# XM-JLINK-V1_0_0.net
KiCad netlist of a schematic drawn in Altium Designer
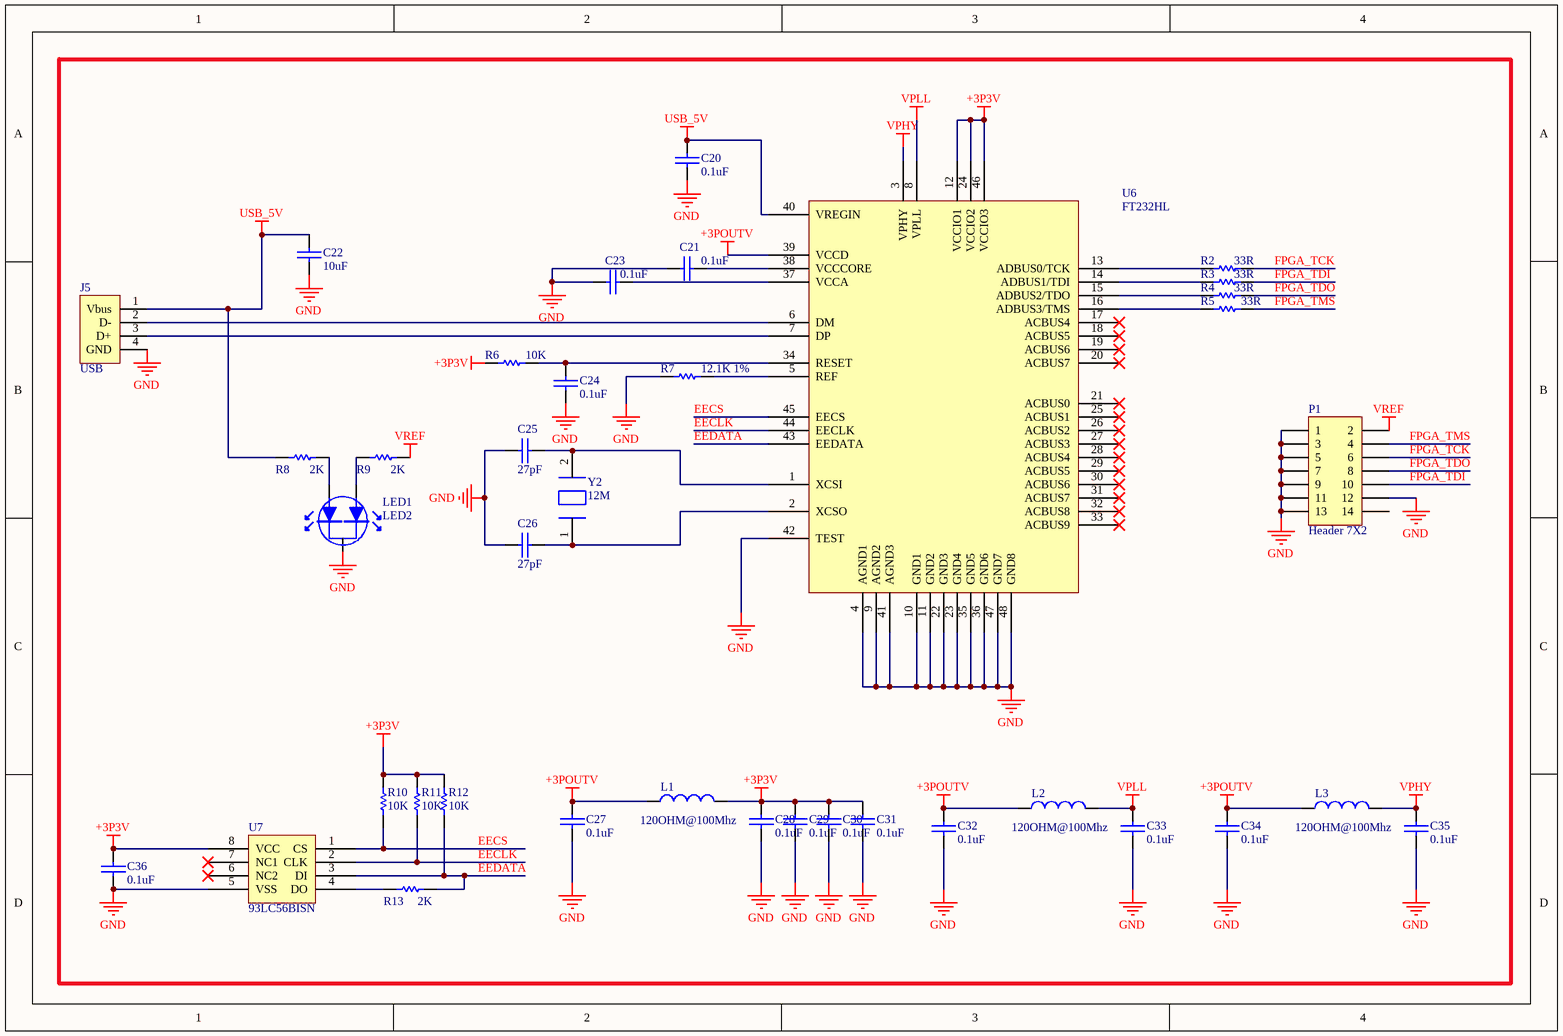
[diagram p0: XM-JLINK-V1.0.0.SchDoc]

(export (version "E")
  (design (tool "Eeschema 10.0.6"))
  (components
    (comp (ref "C20")
      (value "0.1uF")
      (footprint "LC-0603_C")
      (description "Capacitor")
      (libsource (lib "*") (part "CAP"))
    )
    (comp (ref "C21")
      (value "0.1uF")
      (footprint "LC-0603_C")
      (description "Capacitor")
      (libsource (lib "*") (part "CAP"))
    )
    (comp (ref "C22")
      (value "10uF")
      (footprint "C1206")
      (description "Capacitor")
      (libsource (lib "*") (part "CAP"))
    )
    (comp (ref "C23")
      (value "0.1uF")
      (footprint "LC-0603_C")
      (description "Capacitor")
      (libsource (lib "*") (part "CAP"))
    )
    (comp (ref "C24")
      (value "0.1uF")
      (footprint "LC-0603_C")
      (description "Capacitor")
      (libsource (lib "*") (part "CAP"))
    )
    (comp (ref "C25")
      (value "27pF")
      (footprint "LC-0603_C")
      (description "Capacitor")
      (libsource (lib "*") (part "CAP"))
    )
    (comp (ref "C26")
      (value "27pF")
      (footprint "LC-0603_C")
      (description "Capacitor")
      (libsource (lib "*") (part "CAP"))
    )
    (comp (ref "C27")
      (value "0.1uF")
      (footprint "LC-0603_C")
      (description "Capacitor")
      (libsource (lib "*") (part "CAP"))
    )
    (comp (ref "C28")
      (value "0.1uF")
      (footprint "LC-0603_C")
      (description "Capacitor")
      (libsource (lib "*") (part "CAP"))
    )
    (comp (ref "C29")
      (value "0.1uF")
      (footprint "LC-0603_C")
      (description "Capacitor")
      (libsource (lib "*") (part "CAP"))
    )
    (comp (ref "C30")
      (value "0.1uF")
      (footprint "LC-0603_C")
      (description "Capacitor")
      (libsource (lib "*") (part "CAP"))
    )
    (comp (ref "C31")
      (value "0.1uF")
      (footprint "LC-0603_C")
      (description "Capacitor")
      (libsource (lib "*") (part "CAP"))
    )
    (comp (ref "C32")
      (value "0.1uF")
      (footprint "LC-0603_C")
      (description "Capacitor")
      (libsource (lib "*") (part "CAP"))
    )
    (comp (ref "C33")
      (value "0.1uF")
      (footprint "LC-0603_C")
      (description "Capacitor")
      (libsource (lib "*") (part "CAP"))
    )
    (comp (ref "C34")
      (value "0.1uF")
      (footprint "LC-0603_C")
      (description "Capacitor")
      (libsource (lib "*") (part "CAP"))
    )
    (comp (ref "C35")
      (value "0.1uF")
      (footprint "LC-0603_C")
      (description "Capacitor")
      (libsource (lib "*") (part "CAP"))
    )
    (comp (ref "C36")
      (value "0.1uF")
      (footprint "LC-0603_C")
      (description "Capacitor")
      (libsource (lib "*") (part "CAP"))
    )
    (comp (ref "J5")
      (value "USB")
      (footprint "USB-B")
      (description "Header, 4-Pin")
      (fields (field (name "PUBLISHER") "Altium Limited"))
      (libsource (lib "Miscellaneous Connectors") (part "Header 4"))
    )
    (comp (ref "L1")
      (value "120OHM@100Mhz")
      (footprint "LC-0603_L")
      (description "Inductor")
      (fields (field (name "PUBLISHER") "Altium Limited"))
      (libsource (lib "Miscellaneous Devices") (part "Inductor"))
    )
    (comp (ref "L2")
      (value "120OHM@100Mhz")
      (footprint "LC-0603_L")
      (description "Inductor")
      (fields (field (name "PUBLISHER") "Altium Limited"))
      (libsource (lib "Miscellaneous Devices") (part "Inductor"))
    )
    (comp (ref "L3")
      (value "120OHM@100Mhz")
      (footprint "LC-0603_L")
      (description "Inductor")
      (fields (field (name "PUBLISHER") "Altium Limited"))
      (libsource (lib "Miscellaneous Devices") (part "Inductor"))
    )
    (comp (ref "LED1") (value "LED2") (footprint "HDR1X3") (libsource (lib "Schlib1") (part "LED2")))
    (comp (ref "P1")
      (value "Header 7X2")
      (footprint "HDR2X14")
      (description "Header, 7-Pin, Dual row")
      (fields (field (name "PUBLISHER") "Altium Limited"))
      (libsource (lib "Miscellaneous Connectors") (part "Header 7X2"))
    )
    (comp (ref "R2")
      (value "33R")
      (footprint "LC-0603_R")
      (description "Resistor")
      (fields (field (name "Comment") "Res1") (field (name "PUBLISHER") "Altium Limited"))
      (libsource (lib "Miscellaneous Devices") (part "Res1"))
    )
    (comp (ref "R3")
      (value "33R")
      (footprint "LC-0603_R")
      (description "Resistor")
      (fields (field (name "Comment") "Res1") (field (name "PUBLISHER") "Altium Limited"))
      (libsource (lib "Miscellaneous Devices") (part "Res1"))
    )
    (comp (ref "R4")
      (value "33R")
      (footprint "LC-0603_R")
      (description "Resistor")
      (fields (field (name "Comment") "Res1") (field (name "PUBLISHER") "Altium Limited"))
      (libsource (lib "Miscellaneous Devices") (part "Res1"))
    )
    (comp (ref "R5")
      (value "33R")
      (footprint "LC-0603_R")
      (description "Resistor")
      (fields (field (name "Comment") "Res1") (field (name "PUBLISHER") "Altium Limited"))
      (libsource (lib "Miscellaneous Devices") (part "Res1"))
    )
    (comp (ref "R6")
      (value "10K")
      (footprint "LC-0603_R")
      (description "Resistor")
      (fields (field (name "Comment") "Res1") (field (name "PUBLISHER") "Altium Limited"))
      (libsource (lib "Miscellaneous Devices") (part "Res1"))
    )
    (comp (ref "R7")
      (value "12.1K 1%")
      (footprint "LC-0603_R")
      (description "Resistor")
      (fields (field (name "Comment") "Res1") (field (name "PUBLISHER") "Altium Limited"))
      (libsource (lib "Miscellaneous Devices") (part "Res1"))
    )
    (comp (ref "R8")
      (value "2K")
      (footprint "LC-0603_R")
      (description "Resistor")
      (fields (field (name "Comment") "Res1") (field (name "PUBLISHER") "Altium Limited"))
      (libsource (lib "Miscellaneous Devices") (part "Res1"))
    )
    (comp (ref "R9")
      (value "2K")
      (footprint "LC-0603_R")
      (description "Resistor")
      (fields (field (name "Comment") "Res1") (field (name "PUBLISHER") "Altium Limited"))
      (libsource (lib "Miscellaneous Devices") (part "Res1"))
    )
    (comp (ref "R10")
      (value "10K")
      (footprint "LC-0603_R")
      (description "Resistor")
      (fields (field (name "Comment") "Res1") (field (name "PUBLISHER") "Altium Limited"))
      (libsource (lib "Miscellaneous Devices") (part "Res1"))
    )
    (comp (ref "R11")
      (value "10K")
      (footprint "LC-0603_R")
      (description "Resistor")
      (fields (field (name "Comment") "Res1") (field (name "PUBLISHER") "Altium Limited"))
      (libsource (lib "Miscellaneous Devices") (part "Res1"))
    )
    (comp (ref "R12")
      (value "10K")
      (footprint "LC-0603_R")
      (description "Resistor")
      (fields (field (name "Comment") "Res1") (field (name "PUBLISHER") "Altium Limited"))
      (libsource (lib "Miscellaneous Devices") (part "Res1"))
    )
    (comp (ref "R13")
      (value "2K")
      (footprint "LC-0603_L")
      (description "Resistor")
      (fields (field (name "Comment") "Res1") (field (name "PUBLISHER") "Altium Limited"))
      (libsource (lib "Miscellaneous Devices") (part "Res1"))
    )
    (comp (ref "U6") (value "FT232HL") (libsource (lib "Schlib1") (part "FT232HL")))
    (comp (ref "U7")
      (value "93LC56BISN")
      (footprint "LC-SOIC-8_150mil")
      (libsource (lib "Schlib1") (part "93LC56BISN"))
    )
    (comp (ref "Y2") (value "12M") (footprint "CRYSTAL") (libsource (lib "*") (part "XTAL")))
  )
  (nets
    (net (code "1") (name "+3P3V") (class "Default")
      (node (ref "C28") (pin "1") (pinfunction "1_1") (pintype "passive"))
      (node (ref "C29") (pin "1") (pinfunction "1_1") (pintype "passive"))
      (node (ref "C30") (pin "1") (pinfunction "1_1") (pintype "passive"))
      (node (ref "C31") (pin "1") (pinfunction "1_1") (pintype "passive"))
      (node (ref "C36") (pin "1") (pinfunction "1_1") (pintype "passive"))
      (node (ref "L1") (pin "2") (pinfunction "2_2") (pintype "passive"))
      (node (ref "R10") (pin "2") (pinfunction "2_2") (pintype "passive"))
      (node (ref "R11") (pin "2") (pinfunction "2_2") (pintype "passive"))
      (node (ref "R12") (pin "2") (pinfunction "2_2") (pintype "passive"))
      (node (ref "R6") (pin "1") (pinfunction "1_1") (pintype "passive"))
      (node (ref "U6") (pin "12") (pinfunction "VCCIO1_12") (pintype "passive"))
      (node (ref "U6") (pin "24") (pinfunction "VCCIO2_24") (pintype "passive"))
      (node (ref "U6") (pin "46") (pinfunction "VCCIO3_46") (pintype "passive"))
      (node (ref "U7") (pin "8") (pinfunction "VCC_8") (pintype "passive"))
    )
    (net (code "2") (name "+3POUTV") (class "Default")
      (node (ref "C27") (pin "1") (pinfunction "1_1") (pintype "passive"))
      (node (ref "C32") (pin "1") (pinfunction "1_1") (pintype "passive"))
      (node (ref "C34") (pin "1") (pinfunction "1_1") (pintype "passive"))
      (node (ref "L1") (pin "1") (pinfunction "1_1") (pintype "passive"))
      (node (ref "L2") (pin "1") (pinfunction "1_1") (pintype "passive"))
      (node (ref "L3") (pin "1") (pinfunction "1_1") (pintype "passive"))
      (node (ref "U6") (pin "39") (pinfunction "VCCD_39") (pintype "passive"))
    )
    (net (code "3") (name "/EECLK") (class "Default")
      (node (ref "R11") (pin "1") (pinfunction "1_1") (pintype "passive"))
      (node (ref "U6") (pin "44") (pinfunction "EECLK_44") (pintype "passive"))
      (node (ref "U7") (pin "2") (pinfunction "CLK_2") (pintype "passive"))
    )
    (net (code "4") (name "/EECS") (class "Default")
      (node (ref "R10") (pin "1") (pinfunction "1_1") (pintype "passive"))
      (node (ref "U6") (pin "45") (pinfunction "EECS_45") (pintype "passive"))
      (node (ref "U7") (pin "1") (pinfunction "CS_1") (pintype "passive"))
    )
    (net (code "5") (name "/EEDATA") (class "Default")
      (node (ref "R12") (pin "1") (pinfunction "1_1") (pintype "passive"))
      (node (ref "R13") (pin "1") (pinfunction "1_1") (pintype "passive"))
      (node (ref "U6") (pin "43") (pinfunction "EEDATA_43") (pintype "passive"))
      (node (ref "U7") (pin "3") (pinfunction "DI_3") (pintype "passive"))
    )
    (net (code "6") (name "/FPGA_TCK") (class "Default")
      (node (ref "P1") (pin "6") (pinfunction "6_6") (pintype "passive"))
      (node (ref "R2") (pin "2") (pinfunction "2_2") (pintype "passive"))
    )
    (net (code "7") (name "/FPGA_TDI") (class "Default")
      (node (ref "P1") (pin "10") (pinfunction "10_10") (pintype "passive"))
      (node (ref "R3") (pin "2") (pinfunction "2_2") (pintype "passive"))
    )
    (net (code "8") (name "/FPGA_TDO") (class "Default")
      (node (ref "P1") (pin "8") (pinfunction "8_8") (pintype "passive"))
      (node (ref "R4") (pin "2") (pinfunction "2_2") (pintype "passive"))
    )
    (net (code "9") (name "/FPGA_TMS") (class "Default")
      (node (ref "P1") (pin "4") (pinfunction "4_4") (pintype "passive"))
      (node (ref "R5") (pin "2") (pinfunction "2_2") (pintype "passive"))
    )
    (net (code "10") (name "GND") (class "Default")
      (node (ref "C20") (pin "2") (pinfunction "2_2") (pintype "passive"))
      (node (ref "C21") (pin "2") (pinfunction "2_2") (pintype "passive"))
      (node (ref "C22") (pin "2") (pinfunction "2_2") (pintype "passive"))
      (node (ref "C23") (pin "2") (pinfunction "2_2") (pintype "passive"))
      (node (ref "C24") (pin "1") (pinfunction "1_1") (pintype "passive"))
      (node (ref "C25") (pin "1") (pinfunction "1_1") (pintype "passive"))
      (node (ref "C26") (pin "2") (pinfunction "2_2") (pintype "passive"))
      (node (ref "C27") (pin "2") (pinfunction "2_2") (pintype "passive"))
      (node (ref "C28") (pin "2") (pinfunction "2_2") (pintype "passive"))
      (node (ref "C29") (pin "2") (pinfunction "2_2") (pintype "passive"))
      (node (ref "C30") (pin "2") (pinfunction "2_2") (pintype "passive"))
      (node (ref "C31") (pin "2") (pinfunction "2_2") (pintype "passive"))
      (node (ref "C32") (pin "2") (pinfunction "2_2") (pintype "passive"))
      (node (ref "C33") (pin "2") (pinfunction "2_2") (pintype "passive"))
      (node (ref "C34") (pin "2") (pinfunction "2_2") (pintype "passive"))
      (node (ref "C35") (pin "2") (pinfunction "2_2") (pintype "passive"))
      (node (ref "C36") (pin "2") (pinfunction "2_2") (pintype "passive"))
      (node (ref "J5") (pin "4") (pinfunction "GND_4") (pintype "passive"))
      (node (ref "LED1") (pin "2") (pinfunction "2_2") (pintype "passive"))
      (node (ref "P1") (pin "1") (pinfunction "1_1") (pintype "passive"))
      (node (ref "P1") (pin "11") (pinfunction "11_11") (pintype "passive"))
      (node (ref "P1") (pin "12") (pinfunction "12_12") (pintype "passive"))
      (node (ref "P1") (pin "13") (pinfunction "13_13") (pintype "passive"))
      (node (ref "P1") (pin "3") (pinfunction "3_3") (pintype "passive"))
      (node (ref "P1") (pin "5") (pinfunction "5_5") (pintype "passive"))
      (node (ref "P1") (pin "7") (pinfunction "7_7") (pintype "passive"))
      (node (ref "P1") (pin "9") (pinfunction "9_9") (pintype "passive"))
      (node (ref "R7") (pin "1") (pinfunction "1_1") (pintype "passive"))
      (node (ref "U6") (pin "10") (pinfunction "GND1_10") (pintype "passive"))
      (node (ref "U6") (pin "11") (pinfunction "GND2_11") (pintype "passive"))
      (node (ref "U6") (pin "22") (pinfunction "GND3_22") (pintype "passive"))
      (node (ref "U6") (pin "23") (pinfunction "GND4_23") (pintype "passive"))
      (node (ref "U6") (pin "35") (pinfunction "GND5_35") (pintype "passive"))
      (node (ref "U6") (pin "36") (pinfunction "GND6_36") (pintype "passive"))
      (node (ref "U6") (pin "4") (pinfunction "AGND1_4") (pintype "passive"))
      (node (ref "U6") (pin "41") (pinfunction "AGND3_41") (pintype "passive"))
      (node (ref "U6") (pin "42") (pinfunction "TEST_42") (pintype "passive"))
      (node (ref "U6") (pin "47") (pinfunction "GND7_47") (pintype "passive"))
      (node (ref "U6") (pin "48") (pinfunction "GND8_48") (pintype "passive"))
      (node (ref "U6") (pin "9") (pinfunction "AGND2_9") (pintype "passive"))
      (node (ref "U7") (pin "5") (pinfunction "VSS_5") (pintype "passive"))
    )
    (net (code "11") (name "Net-(J5-D+)") (class "Default")
      (node (ref "J5") (pin "3") (pinfunction "D+_3") (pintype "passive"))
      (node (ref "U6") (pin "7") (pinfunction "DP_7") (pintype "passive"))
    )
    (net (code "12") (name "Net-(J5-D-)") (class "Default")
      (node (ref "J5") (pin "2") (pinfunction "D-_2") (pintype "passive"))
      (node (ref "U6") (pin "6") (pinfunction "DM_6") (pintype "passive"))
    )
    (net (code "13") (name "Net-(LED1-Pad1)") (class "Default")
      (node (ref "LED1") (pin "1") (pinfunction "1_1") (pintype "passive"))
      (node (ref "R8") (pin "1") (pinfunction "1_1") (pintype "passive"))
    )
    (net (code "14") (name "Net-(LED1-Pad3)") (class "Default")
      (node (ref "LED1") (pin "3") (pinfunction "3_3") (pintype "passive"))
      (node (ref "R9") (pin "2") (pinfunction "2_2") (pintype "passive"))
    )
    (net (code "15") (name "Net-(U6-ADBUS0{slash}TCK)") (class "Default")
      (node (ref "R2") (pin "1") (pinfunction "1_1") (pintype "passive"))
      (node (ref "U6") (pin "13") (pinfunction "ADBUS0/TCK_13") (pintype "passive"))
    )
    (net (code "16") (name "Net-(U6-ADBUS1{slash}TDI)") (class "Default")
      (node (ref "R3") (pin "1") (pinfunction "1_1") (pintype "passive"))
      (node (ref "U6") (pin "14") (pinfunction "ADBUS1/TDI_14") (pintype "passive"))
    )
    (net (code "17") (name "Net-(U6-ADBUS2{slash}TDO)") (class "Default")
      (node (ref "R4") (pin "1") (pinfunction "1_1") (pintype "passive"))
      (node (ref "U6") (pin "15") (pinfunction "ADBUS2/TDO_15") (pintype "passive"))
    )
    (net (code "18") (name "Net-(U6-ADBUS3{slash}TMS)") (class "Default")
      (node (ref "R5") (pin "1") (pinfunction "1_1") (pintype "passive"))
      (node (ref "U6") (pin "16") (pinfunction "ADBUS3/TMS_16") (pintype "passive"))
    )
    (net (code "19") (name "Net-(U6-REF)") (class "Default")
      (node (ref "R7") (pin "2") (pinfunction "2_2") (pintype "passive"))
      (node (ref "U6") (pin "5") (pinfunction "REF_5") (pintype "passive"))
    )
    (net (code "20") (name "Net-(U6-RESET)") (class "Default")
      (node (ref "C24") (pin "2") (pinfunction "2_2") (pintype "passive"))
      (node (ref "R6") (pin "2") (pinfunction "2_2") (pintype "passive"))
      (node (ref "U6") (pin "34") (pinfunction "RESET_34") (pintype "passive"))
    )
    (net (code "21") (name "Net-(U6-VCCA)") (class "Default")
      (node (ref "C23") (pin "1") (pinfunction "1_1") (pintype "passive"))
      (node (ref "U6") (pin "37") (pinfunction "VCCA_37") (pintype "passive"))
    )
    (net (code "22") (name "Net-(U6-VCCCORE)") (class "Default")
      (node (ref "C21") (pin "1") (pinfunction "1_1") (pintype "passive"))
      (node (ref "U6") (pin "38") (pinfunction "VCCCORE_38") (pintype "passive"))
    )
    (net (code "23") (name "Net-(U6-XCSI)") (class "Default")
      (node (ref "C25") (pin "2") (pinfunction "2_2") (pintype "passive"))
      (node (ref "U6") (pin "1") (pinfunction "XCSI_1") (pintype "passive"))
      (node (ref "Y2") (pin "2") (pintype "passive"))
    )
    (net (code "24") (name "Net-(U6-XCSO)") (class "Default")
      (node (ref "C26") (pin "1") (pinfunction "1_1") (pintype "passive"))
      (node (ref "U6") (pin "2") (pinfunction "XCSO_2") (pintype "passive"))
      (node (ref "Y2") (pin "1") (pintype "passive"))
    )
    (net (code "25") (name "Net-(U7-DO)") (class "Default")
      (node (ref "R13") (pin "2") (pinfunction "2_2") (pintype "passive"))
      (node (ref "U7") (pin "4") (pinfunction "DO_4") (pintype "passive"))
    )
    (net (code "26") (name "USB_5V") (class "Default")
      (node (ref "C20") (pin "1") (pinfunction "1_1") (pintype "passive"))
      (node (ref "C22") (pin "1") (pinfunction "1_1") (pintype "passive"))
      (node (ref "J5") (pin "1") (pinfunction "Vbus_1") (pintype "passive"))
      (node (ref "R8") (pin "2") (pinfunction "2_2") (pintype "passive"))
      (node (ref "U6") (pin "40") (pinfunction "VREGIN_40") (pintype "passive"))
    )
    (net (code "27") (name "VPHY") (class "Default")
      (node (ref "C35") (pin "1") (pinfunction "1_1") (pintype "passive"))
      (node (ref "L3") (pin "2") (pinfunction "2_2") (pintype "passive"))
      (node (ref "U6") (pin "3") (pinfunction "VPHY_3") (pintype "passive"))
    )
    (net (code "28") (name "VPLL") (class "Default")
      (node (ref "C33") (pin "1") (pinfunction "1_1") (pintype "passive"))
      (node (ref "L2") (pin "2") (pinfunction "2_2") (pintype "passive"))
      (node (ref "U6") (pin "8") (pinfunction "VPLL_8") (pintype "passive"))
    )
    (net (code "29") (name "VREF") (class "Default")
      (node (ref "P1") (pin "2") (pinfunction "2_2") (pintype "passive"))
      (node (ref "R9") (pin "1") (pinfunction "1_1") (pintype "passive"))
    )
    (net (code "30") (name "unconnected-(P1-Pad14)") (class "Default")
      (node (ref "P1") (pin "14") (pinfunction "14_14") (pintype "passive"))
    )
    (net (code "31") (name "unconnected-(U6-ACBUS0-Pad21)") (class "Default")
      (node (ref "U6") (pin "21") (pinfunction "ACBUS0_21") (pintype "passive+no_connect"))
    )
    (net (code "32") (name "unconnected-(U6-ACBUS1-Pad25)") (class "Default")
      (node (ref "U6") (pin "25") (pinfunction "ACBUS1_25") (pintype "passive+no_connect"))
    )
    (net (code "33") (name "unconnected-(U6-ACBUS2-Pad26)") (class "Default")
      (node (ref "U6") (pin "26") (pinfunction "ACBUS2_26") (pintype "passive+no_connect"))
    )
    (net (code "34") (name "unconnected-(U6-ACBUS3-Pad27)") (class "Default")
      (node (ref "U6") (pin "27") (pinfunction "ACBUS3_27") (pintype "passive+no_connect"))
    )
    (net (code "35") (name "unconnected-(U6-ACBUS4-Pad17)") (class "Default")
      (node (ref "U6") (pin "17") (pinfunction "ACBUS4_17") (pintype "passive+no_connect"))
    )
    (net (code "36") (name "unconnected-(U6-ACBUS4-Pad28)") (class "Default")
      (node (ref "U6") (pin "28") (pinfunction "ACBUS4_28") (pintype "passive+no_connect"))
    )
    (net (code "37") (name "unconnected-(U6-ACBUS5-Pad18)") (class "Default")
      (node (ref "U6") (pin "18") (pinfunction "ACBUS5_18") (pintype "passive+no_connect"))
    )
    (net (code "38") (name "unconnected-(U6-ACBUS5-Pad29)") (class "Default")
      (node (ref "U6") (pin "29") (pinfunction "ACBUS5_29") (pintype "passive+no_connect"))
    )
    (net (code "39") (name "unconnected-(U6-ACBUS6-Pad19)") (class "Default")
      (node (ref "U6") (pin "19") (pinfunction "ACBUS6_19") (pintype "passive+no_connect"))
    )
    (net (code "40") (name "unconnected-(U6-ACBUS6-Pad30)") (class "Default")
      (node (ref "U6") (pin "30") (pinfunction "ACBUS6_30") (pintype "passive+no_connect"))
    )
    (net (code "41") (name "unconnected-(U6-ACBUS7-Pad20)") (class "Default")
      (node (ref "U6") (pin "20") (pinfunction "ACBUS7_20") (pintype "passive+no_connect"))
    )
    (net (code "42") (name "unconnected-(U6-ACBUS7-Pad31)") (class "Default")
      (node (ref "U6") (pin "31") (pinfunction "ACBUS7_31") (pintype "passive+no_connect"))
    )
    (net (code "43") (name "unconnected-(U6-ACBUS8-Pad32)") (class "Default")
      (node (ref "U6") (pin "32") (pinfunction "ACBUS8_32") (pintype "passive+no_connect"))
    )
    (net (code "44") (name "unconnected-(U6-ACBUS9-Pad33)") (class "Default")
      (node (ref "U6") (pin "33") (pinfunction "ACBUS9_33") (pintype "passive+no_connect"))
    )
    (net (code "45") (name "unconnected-(U7-NC1-Pad7)") (class "Default")
      (node (ref "U7") (pin "7") (pinfunction "NC1_7") (pintype "passive+no_connect"))
    )
    (net (code "46") (name "unconnected-(U7-NC2-Pad6)") (class "Default")
      (node (ref "U7") (pin "6") (pinfunction "NC2_6") (pintype "passive+no_connect"))
    )
  )
)
